# G031_Dev.net
KiCad netlist of a schematic drawn in Altium Designer
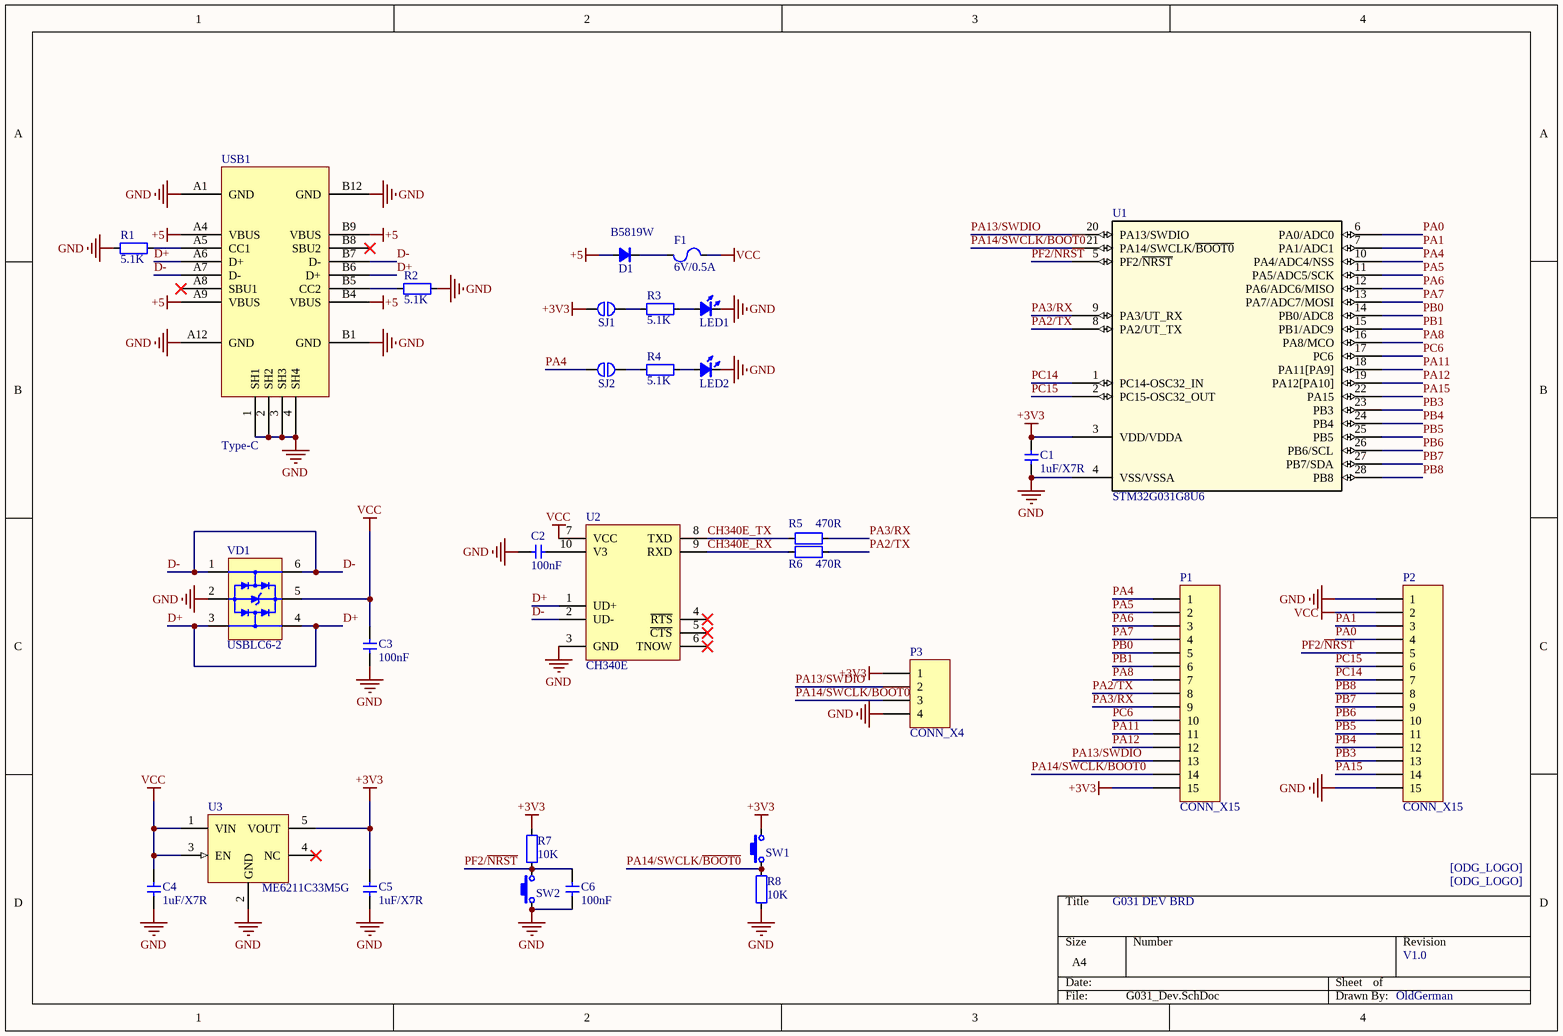
[diagram p0: G031_Dev.SchDoc]

(export (version "E")
  (design (tool "Eeschema 10.0.6"))
  (components
    (comp (ref "*1")
      (value "ODG_LOGO")
      (footprint "ODG_LOGO")
      (libsource (lib "ODG_AD_Lib") (part "ODG_LOGO"))
    )
    (comp (ref "*2")
      (value "ODG_LOGO")
      (footprint "ODG_LOGO")
      (libsource (lib "ODG_AD_Lib") (part "ODG_LOGO"))
    )
    (comp (ref "C1")
      (value "1uF/X7R")
      (footprint "C0603")
      (description "Capacitor")
      (libsource (lib "ODG_AD_Lib") (part "CAP"))
    )
    (comp (ref "C2")
      (value "100nF")
      (footprint "C0603")
      (description "Capacitor")
      (libsource (lib "ODG_AD_Lib") (part "CAP"))
    )
    (comp (ref "C3")
      (value "100nF")
      (footprint "C0603")
      (description "Capacitor")
      (libsource (lib "ODG_AD_Lib") (part "CAP"))
    )
    (comp (ref "C4")
      (value "1uF/X7R")
      (footprint "C0603")
      (description "Capacitor")
      (libsource (lib "ODG_AD_Lib") (part "CAP"))
    )
    (comp (ref "C5")
      (value "1uF/X7R")
      (footprint "C0603")
      (description "Capacitor")
      (libsource (lib "ODG_AD_Lib") (part "CAP"))
    )
    (comp (ref "C6")
      (value "100nF")
      (footprint "C0603")
      (description "Capacitor")
      (libsource (lib "ODG_AD_Lib") (part "CAP"))
    )
    (comp (ref "D1")
      (value "B5819W")
      (footprint "SOD-323")
      (description "二极管")
      (libsource (lib "ODG_AD_Lib") (part "DIODE"))
    )
    (comp (ref "F1")
      (value "6V/0.5A")
      (footprint "FUSE0603_0.5MM")
      (description "贴片自恢复保险丝")
      (libsource (lib "ODG_AD_Lib") (part "FUSE"))
    )
    (comp (ref "LED1") (value "LED") (footprint "LED0603_GREEN") (libsource (lib "ODG_AD_Lib") (part "LED")))
    (comp (ref "LED2") (value "LED") (footprint "LED0603_YELLOW") (libsource (lib "ODG_AD_Lib") (part "LED")))
    (comp (ref "P1")
      (value "CONN_X15")
      (footprint "2.54MM_MALE_X15")
      (libsource (lib "ODG_AD_Lib") (part "CONN_X15"))
    )
    (comp (ref "P2")
      (value "CONN_X15")
      (footprint "2.54MM_MALE_X15")
      (libsource (lib "ODG_AD_Lib") (part "CONN_X15"))
    )
    (comp (ref "P3")
      (value "CONN_X4")
      (footprint "2.54mm_Male_x4")
      (libsource (lib "ODG_AD_Lib") (part "CONN_X4"))
    )
    (comp (ref "R1")
      (value "5.1K")
      (footprint "R0603")
      (description "Resistor")
      (libsource (lib "ODG_AD_Lib") (part "RES"))
    )
    (comp (ref "R2")
      (value "5.1K")
      (footprint "R0603")
      (description "Resistor")
      (libsource (lib "ODG_AD_Lib") (part "RES"))
    )
    (comp (ref "R3")
      (value "5.1K")
      (footprint "R0603")
      (description "Resistor")
      (libsource (lib "ODG_AD_Lib") (part "RES"))
    )
    (comp (ref "R4")
      (value "5.1K")
      (footprint "R0603")
      (description "Resistor")
      (libsource (lib "ODG_AD_Lib") (part "RES"))
    )
    (comp (ref "R5")
      (value "470R")
      (footprint "R0603")
      (description "Resistor")
      (libsource (lib "ODG_AD_Lib") (part "RES"))
    )
    (comp (ref "R6")
      (value "470R")
      (footprint "R0603")
      (description "Resistor")
      (libsource (lib "ODG_AD_Lib") (part "RES"))
    )
    (comp (ref "R7")
      (value "10K")
      (footprint "R0603")
      (description "Resistor")
      (libsource (lib "") (part "RES_1"))
    )
    (comp (ref "R8")
      (value "10K")
      (footprint "R0603")
      (description "Resistor")
      (libsource (lib "") (part "RES_1"))
    )
    (comp (ref "SJ1")
      (value "SJ_2P")
      (footprint "SJ_2P_MINI")
      (description "焊接跳线")
      (libsource (lib "ODG_AD_Lib") (part "SJ_2P"))
    )
    (comp (ref "SJ2")
      (value "SJ_2P")
      (footprint "SJ_2P_MINI")
      (description "焊接跳线")
      (libsource (lib "ODG_AD_Lib") (part "SJ_2P"))
    )
    (comp (ref "SW1")
      (value "Button-2P")
      (footprint "SWITCH_3X4_SMD")
      (description "Button")
      (libsource (lib "ODG_AD_Lib") (part "Button-2P"))
    )
    (comp (ref "SW2")
      (value "Button-2P")
      (footprint "SWITCH_3X4_SMD")
      (description "Button")
      (libsource (lib "ODG_AD_Lib") (part "Button-2P"))
    )
    (comp (ref "U1")
      (value "STM32G031G8U6")
      (footprint "UFQFPN28-4x4mm_ODG")
      (description "No Description Available")
      (fields (field (name "COPYRIGHT") "Copyright (C) 2022 Ultra Librarian. All rights reserved."))
      (libsource (lib "ODG_AD_Lib") (part "STM32G031G8U6"))
    )
    (comp (ref "U2")
      (value "CH340E")
      (footprint "TI MSOP-10 DGS")
      (libsource (lib "ODG_AD_Lib") (part "CH340E"))
    )
    (comp (ref "U3")
      (value "ME6211C33M5G")
      (footprint "ANALOG TSOT-23-5 UJ-5")
      (description "线性稳压芯片")
      (fields (field (name "版权归属") "源创客"))
      (libsource (lib "ODG_AD_Lib") (part "ME6211C33M5G"))
    )
    (comp (ref "USB1")
      (value "Type-C")
      (footprint "Type-C-TOP")
      (libsource (lib "ODG_AD_Lib") (part "USB-Type-C_16P"))
    )
    (comp (ref "VD1")
      (value "USBLC6-2")
      (footprint "MICROCHIP SOT-23-6 M6")
      (fields (field (name "版权归属") "源创客"))
      (libsource (lib "ODG_AD_Lib") (part "USBLC6-2"))
    )
  )
  (nets
    (net (code "1") (name "+3V3") (class "Default")
      (node (ref "C1") (pin "1") (pinfunction "1_1") (pintype "passive"))
      (node (ref "C5") (pin "2") (pinfunction "2_2") (pintype "passive"))
      (node (ref "P1") (pin "15") (pinfunction "15_15") (pintype "passive"))
      (node (ref "P3") (pin "1") (pinfunction "1_1") (pintype "passive"))
      (node (ref "R7") (pin "1") (pinfunction "1_1") (pintype "passive"))
      (node (ref "SJ1") (pin "1") (pinfunction "1_1") (pintype "passive"))
      (node (ref "SW1") (pin "2") (pinfunction "2_2") (pintype "passive"))
      (node (ref "U1") (pin "3") (pinfunction "VDD/VDDA_3") (pintype "power_in"))
      (node (ref "U3") (pin "5") (pinfunction "VOUT_5") (pintype "passive"))
    )
    (net (code "2") (name "+5") (class "Default")
      (node (ref "D1") (pin "1") (pinfunction "A_1") (pintype "passive"))
      (node (ref "USB1") (pin "A4") (pinfunction "VBUS_A4") (pintype "passive"))
      (node (ref "USB1") (pin "A9") (pinfunction "VBUS_A9") (pintype "passive"))
      (node (ref "USB1") (pin "B4") (pinfunction "VBUS_B4") (pintype "passive"))
      (node (ref "USB1") (pin "B9") (pinfunction "VBUS_B9") (pintype "passive"))
    )
    (net (code "3") (name "/CH340E_RX") (class "Default")
      (node (ref "R6") (pin "1") (pinfunction "1_1") (pintype "passive"))
      (node (ref "U2") (pin "9") (pinfunction "RXD_9") (pintype "passive"))
    )
    (net (code "4") (name "/CH340E_TX") (class "Default")
      (node (ref "R5") (pin "1") (pinfunction "1_1") (pintype "passive"))
      (node (ref "U2") (pin "8") (pinfunction "TXD_8") (pintype "passive"))
    )
    (net (code "5") (name "/D+") (class "Default")
      (node (ref "U2") (pin "1") (pinfunction "UD+_1") (pintype "passive"))
      (node (ref "USB1") (pin "A6") (pinfunction "D+_A6") (pintype "passive"))
      (node (ref "USB1") (pin "B6") (pinfunction "D+_B6") (pintype "passive"))
      (node (ref "VD1") (pin "3") (pinfunction "I/O2_3") (pintype "passive"))
      (node (ref "VD1") (pin "4") (pinfunction "I/O2_4") (pintype "passive"))
    )
    (net (code "6") (name "/D-") (class "Default")
      (node (ref "U2") (pin "2") (pinfunction "UD-_2") (pintype "passive"))
      (node (ref "USB1") (pin "A7") (pinfunction "D-_A7") (pintype "passive"))
      (node (ref "USB1") (pin "B7") (pinfunction "D-_B7") (pintype "passive"))
      (node (ref "VD1") (pin "1") (pinfunction "I/O1_1") (pintype "passive"))
      (node (ref "VD1") (pin "6") (pinfunction "I/O1_6") (pintype "passive"))
    )
    (net (code "7") (name "/PA0") (class "Default")
      (node (ref "P2") (pin "4") (pinfunction "4_4") (pintype "passive"))
      (node (ref "U1") (pin "6") (pinfunction "PA0/ADC0_6") (pintype "bidirectional"))
    )
    (net (code "8") (name "/PA1") (class "Default")
      (node (ref "P2") (pin "3") (pinfunction "3_3") (pintype "passive"))
      (node (ref "U1") (pin "7") (pinfunction "PA1/ADC1_7") (pintype "bidirectional"))
    )
    (net (code "9") (name "/PA2{slash}TX") (class "Default")
      (node (ref "P1") (pin "8") (pinfunction "8_8") (pintype "passive"))
      (node (ref "R6") (pin "2") (pinfunction "2_2") (pintype "passive"))
      (node (ref "U1") (pin "8") (pinfunction "PA2/UT_TX_8") (pintype "bidirectional"))
    )
    (net (code "10") (name "/PA3{slash}RX") (class "Default")
      (node (ref "P1") (pin "9") (pinfunction "9_9") (pintype "passive"))
      (node (ref "R5") (pin "2") (pinfunction "2_2") (pintype "passive"))
      (node (ref "U1") (pin "9") (pinfunction "PA3/UT_RX_9") (pintype "bidirectional"))
    )
    (net (code "11") (name "/PA4") (class "Default")
      (node (ref "P1") (pin "1") (pinfunction "1_1") (pintype "passive"))
      (node (ref "SJ2") (pin "1") (pinfunction "1_1") (pintype "passive"))
      (node (ref "U1") (pin "10") (pinfunction "PA4/ADC4/NSS_10") (pintype "bidirectional"))
    )
    (net (code "12") (name "/PA5") (class "Default")
      (node (ref "P1") (pin "2") (pinfunction "2_2") (pintype "passive"))
      (node (ref "U1") (pin "11") (pinfunction "PA5/ADC5/SCK_11") (pintype "bidirectional"))
    )
    (net (code "13") (name "/PA6") (class "Default")
      (node (ref "P1") (pin "3") (pinfunction "3_3") (pintype "passive"))
      (node (ref "U1") (pin "12") (pinfunction "PA6/ADC6/MISO_12") (pintype "bidirectional"))
    )
    (net (code "14") (name "/PA7") (class "Default")
      (node (ref "P1") (pin "4") (pinfunction "4_4") (pintype "passive"))
      (node (ref "U1") (pin "13") (pinfunction "PA7/ADC7/MOSI_13") (pintype "bidirectional"))
    )
    (net (code "15") (name "/PA8") (class "Default")
      (node (ref "P1") (pin "7") (pinfunction "7_7") (pintype "passive"))
      (node (ref "U1") (pin "16") (pinfunction "PA8/MCO_16") (pintype "bidirectional"))
    )
    (net (code "16") (name "/PA11") (class "Default")
      (node (ref "P1") (pin "11") (pinfunction "11_11") (pintype "passive"))
      (node (ref "U1") (pin "18") (pinfunction "PA11[PA9]_18") (pintype "bidirectional"))
    )
    (net (code "17") (name "/PA12") (class "Default")
      (node (ref "P1") (pin "12") (pinfunction "12_12") (pintype "passive"))
      (node (ref "U1") (pin "19") (pinfunction "PA12[PA10]_19") (pintype "bidirectional"))
    )
    (net (code "18") (name "/PA13{slash}SWDIO") (class "Default")
      (node (ref "P1") (pin "13") (pinfunction "13_13") (pintype "passive"))
      (node (ref "P3") (pin "2") (pinfunction "2_2") (pintype "passive"))
      (node (ref "U1") (pin "20") (pinfunction "PA13/SWDIO_20") (pintype "bidirectional"))
    )
    (net (code "19") (name "/PA14{slash}SWCLK{slash}~{BOOT0}") (class "Default")
      (node (ref "P1") (pin "14") (pinfunction "14_14") (pintype "passive"))
      (node (ref "P3") (pin "3") (pinfunction "3_3") (pintype "passive"))
      (node (ref "R8") (pin "1") (pinfunction "1_1") (pintype "passive"))
      (node (ref "SW1") (pin "1") (pinfunction "1_1") (pintype "passive"))
      (node (ref "U1") (pin "21") (pinfunction "PA14/SWCLK/~{BOOT0}_21") (pintype "bidirectional"))
    )
    (net (code "20") (name "/PA15") (class "Default")
      (node (ref "P2") (pin "14") (pinfunction "14_14") (pintype "passive"))
      (node (ref "U1") (pin "22") (pinfunction "PA15_22") (pintype "bidirectional"))
    )
    (net (code "21") (name "/PB0") (class "Default")
      (node (ref "P1") (pin "5") (pinfunction "5_5") (pintype "passive"))
      (node (ref "U1") (pin "14") (pinfunction "PB0/ADC8_14") (pintype "bidirectional"))
    )
    (net (code "22") (name "/PB1") (class "Default")
      (node (ref "P1") (pin "6") (pinfunction "6_6") (pintype "passive"))
      (node (ref "U1") (pin "15") (pinfunction "PB1/ADC9_15") (pintype "bidirectional"))
    )
    (net (code "23") (name "/PB3") (class "Default")
      (node (ref "P2") (pin "13") (pinfunction "13_13") (pintype "passive"))
      (node (ref "U1") (pin "23") (pinfunction "PB3_23") (pintype "bidirectional"))
    )
    (net (code "24") (name "/PB4") (class "Default")
      (node (ref "P2") (pin "12") (pinfunction "12_12") (pintype "passive"))
      (node (ref "U1") (pin "24") (pinfunction "PB4_24") (pintype "bidirectional"))
    )
    (net (code "25") (name "/PB5") (class "Default")
      (node (ref "P2") (pin "11") (pinfunction "11_11") (pintype "passive"))
      (node (ref "U1") (pin "25") (pinfunction "PB5_25") (pintype "bidirectional"))
    )
    (net (code "26") (name "/PB6") (class "Default")
      (node (ref "P2") (pin "10") (pinfunction "10_10") (pintype "passive"))
      (node (ref "U1") (pin "26") (pinfunction "PB6/SCL_26") (pintype "bidirectional"))
    )
    (net (code "27") (name "/PB7") (class "Default")
      (node (ref "P2") (pin "9") (pinfunction "9_9") (pintype "passive"))
      (node (ref "U1") (pin "27") (pinfunction "PB7/SDA_27") (pintype "bidirectional"))
    )
    (net (code "28") (name "/PB8") (class "Default")
      (node (ref "P2") (pin "8") (pinfunction "8_8") (pintype "passive"))
      (node (ref "U1") (pin "28") (pinfunction "PB8_28") (pintype "bidirectional"))
    )
    (net (code "29") (name "/PC6") (class "Default")
      (node (ref "P1") (pin "10") (pinfunction "10_10") (pintype "passive"))
      (node (ref "U1") (pin "17") (pinfunction "PC6_17") (pintype "bidirectional"))
    )
    (net (code "30") (name "/PC14") (class "Default")
      (node (ref "P2") (pin "7") (pinfunction "7_7") (pintype "passive"))
      (node (ref "U1") (pin "1") (pinfunction "PC14-OSC32_IN_1") (pintype "bidirectional"))
    )
    (net (code "31") (name "/PC15") (class "Default")
      (node (ref "P2") (pin "6") (pinfunction "6_6") (pintype "passive"))
      (node (ref "U1") (pin "2") (pinfunction "PC15-OSC32_OUT_2") (pintype "bidirectional"))
    )
    (net (code "32") (name "/PF2{slash}~{NRST}") (class "Default")
      (node (ref "C6") (pin "2") (pinfunction "2_2") (pintype "passive"))
      (node (ref "P2") (pin "5") (pinfunction "5_5") (pintype "passive"))
      (node (ref "R7") (pin "2") (pinfunction "2_2") (pintype "passive"))
      (node (ref "SW2") (pin "2") (pinfunction "2_2") (pintype "passive"))
      (node (ref "U1") (pin "5") (pinfunction "PF2/~{NRST}_5") (pintype "bidirectional"))
    )
    (net (code "33") (name "GND") (class "Default")
      (node (ref "C1") (pin "2") (pinfunction "2_2") (pintype "passive"))
      (node (ref "C2") (pin "1") (pinfunction "1_1") (pintype "passive"))
      (node (ref "C3") (pin "1") (pinfunction "1_1") (pintype "passive"))
      (node (ref "C4") (pin "1") (pinfunction "1_1") (pintype "passive"))
      (node (ref "C5") (pin "1") (pinfunction "1_1") (pintype "passive"))
      (node (ref "C6") (pin "1") (pinfunction "1_1") (pintype "passive"))
      (node (ref "LED1") (pin "2") (pinfunction "K_2") (pintype "passive"))
      (node (ref "LED2") (pin "2") (pinfunction "K_2") (pintype "passive"))
      (node (ref "P2") (pin "1") (pinfunction "1_1") (pintype "passive"))
      (node (ref "P2") (pin "15") (pinfunction "15_15") (pintype "passive"))
      (node (ref "P3") (pin "4") (pinfunction "4_4") (pintype "passive"))
      (node (ref "R1") (pin "1") (pinfunction "1_1") (pintype "passive"))
      (node (ref "R2") (pin "2") (pinfunction "2_2") (pintype "passive"))
      (node (ref "R8") (pin "2") (pinfunction "2_2") (pintype "passive"))
      (node (ref "SW2") (pin "1") (pinfunction "1_1") (pintype "passive"))
      (node (ref "U1") (pin "4") (pinfunction "VSS/VSSA_4") (pintype "power_in"))
      (node (ref "U2") (pin "3") (pinfunction "GND_3") (pintype "passive"))
      (node (ref "U3") (pin "2") (pinfunction "GND_2") (pintype "passive"))
      (node (ref "USB1") (pin "1") (pinfunction "SH1_1") (pintype "passive"))
      (node (ref "USB1") (pin "2") (pinfunction "SH2_2") (pintype "passive"))
      (node (ref "USB1") (pin "3") (pinfunction "SH3_3") (pintype "passive"))
      (node (ref "USB1") (pin "4") (pinfunction "SH4_4") (pintype "passive"))
      (node (ref "USB1") (pin "A1") (pinfunction "GND_A1") (pintype "passive"))
      (node (ref "USB1") (pin "A12") (pinfunction "GND_A12") (pintype "passive"))
      (node (ref "USB1") (pin "B1") (pinfunction "GND_B1") (pintype "passive"))
      (node (ref "USB1") (pin "B12") (pinfunction "GND_B12") (pintype "passive"))
      (node (ref "VD1") (pin "2") (pinfunction "GND_2") (pintype "passive"))
    )
    (net (code "34") (name "Net-(D1-C)") (class "Default")
      (node (ref "D1") (pin "2") (pinfunction "C_2") (pintype "passive"))
      (node (ref "F1") (pin "1") (pinfunction "1_1") (pintype "passive"))
    )
    (net (code "35") (name "Net-(LED1-A)") (class "Default")
      (node (ref "LED1") (pin "1") (pinfunction "A_1") (pintype "passive"))
      (node (ref "R3") (pin "2") (pinfunction "2_2") (pintype "passive"))
    )
    (net (code "36") (name "Net-(LED2-A)") (class "Default")
      (node (ref "LED2") (pin "1") (pinfunction "A_1") (pintype "passive"))
      (node (ref "R4") (pin "2") (pinfunction "2_2") (pintype "passive"))
    )
    (net (code "37") (name "Net-(R3-Pad1)") (class "Default")
      (node (ref "R3") (pin "1") (pinfunction "1_1") (pintype "passive"))
      (node (ref "SJ1") (pin "2") (pinfunction "2_2") (pintype "passive"))
    )
    (net (code "38") (name "Net-(R4-Pad1)") (class "Default")
      (node (ref "R4") (pin "1") (pinfunction "1_1") (pintype "passive"))
      (node (ref "SJ2") (pin "2") (pinfunction "2_2") (pintype "passive"))
    )
    (net (code "39") (name "Net-(U2-V3)") (class "Default")
      (node (ref "C2") (pin "2") (pinfunction "2_2") (pintype "passive"))
      (node (ref "U2") (pin "10") (pinfunction "V3_10") (pintype "passive"))
    )
    (net (code "40") (name "Net-(USB1-CC1)") (class "Default")
      (node (ref "R1") (pin "2") (pinfunction "2_2") (pintype "passive"))
      (node (ref "USB1") (pin "A5") (pinfunction "CC1_A5") (pintype "passive"))
    )
    (net (code "41") (name "Net-(USB1-CC2)") (class "Default")
      (node (ref "R2") (pin "1") (pinfunction "1_1") (pintype "passive"))
      (node (ref "USB1") (pin "B5") (pinfunction "CC2_B5") (pintype "passive"))
    )
    (net (code "42") (name "VCC") (class "Default")
      (node (ref "C3") (pin "2") (pinfunction "2_2") (pintype "passive"))
      (node (ref "C4") (pin "2") (pinfunction "2_2") (pintype "passive"))
      (node (ref "F1") (pin "2") (pinfunction "2_2") (pintype "passive"))
      (node (ref "P2") (pin "2") (pinfunction "2_2") (pintype "passive"))
      (node (ref "U2") (pin "7") (pinfunction "VCC_7") (pintype "passive"))
      (node (ref "U3") (pin "1") (pinfunction "VIN_1") (pintype "passive"))
      (node (ref "U3") (pin "3") (pinfunction "EN_3") (pintype "input"))
      (node (ref "VD1") (pin "5") (pinfunction "VBUS_5") (pintype "passive"))
    )
    (net (code "43") (name "unconnected-(U2-TNOW-Pad6)") (class "Default")
      (node (ref "U2") (pin "6") (pinfunction "TNOW_6") (pintype "passive+no_connect"))
    )
    (net (code "44") (name "unconnected-(U2-~{CTS}-Pad5)") (class "Default")
      (node (ref "U2") (pin "5") (pinfunction "~{CTS}_5") (pintype "passive+no_connect"))
    )
    (net (code "45") (name "unconnected-(U2-~{RTS}-Pad4)") (class "Default")
      (node (ref "U2") (pin "4") (pinfunction "~{RTS}_4") (pintype "passive+no_connect"))
    )
    (net (code "46") (name "unconnected-(U3-NC-Pad4)") (class "Default")
      (node (ref "U3") (pin "4") (pinfunction "NC_4") (pintype "passive+no_connect"))
    )
    (net (code "47") (name "unconnected-(USB1-SBU1-PadA8)") (class "Default")
      (node (ref "USB1") (pin "A8") (pinfunction "SBU1_A8") (pintype "passive+no_connect"))
    )
    (net (code "48") (name "unconnected-(USB1-SBU2-PadB8)") (class "Default")
      (node (ref "USB1") (pin "B8") (pinfunction "SBU2_B8") (pintype "passive+no_connect"))
    )
  )
)
